# Soccer_Esp32.net
KiCad netlist of a schematic drawn in EasyEDA
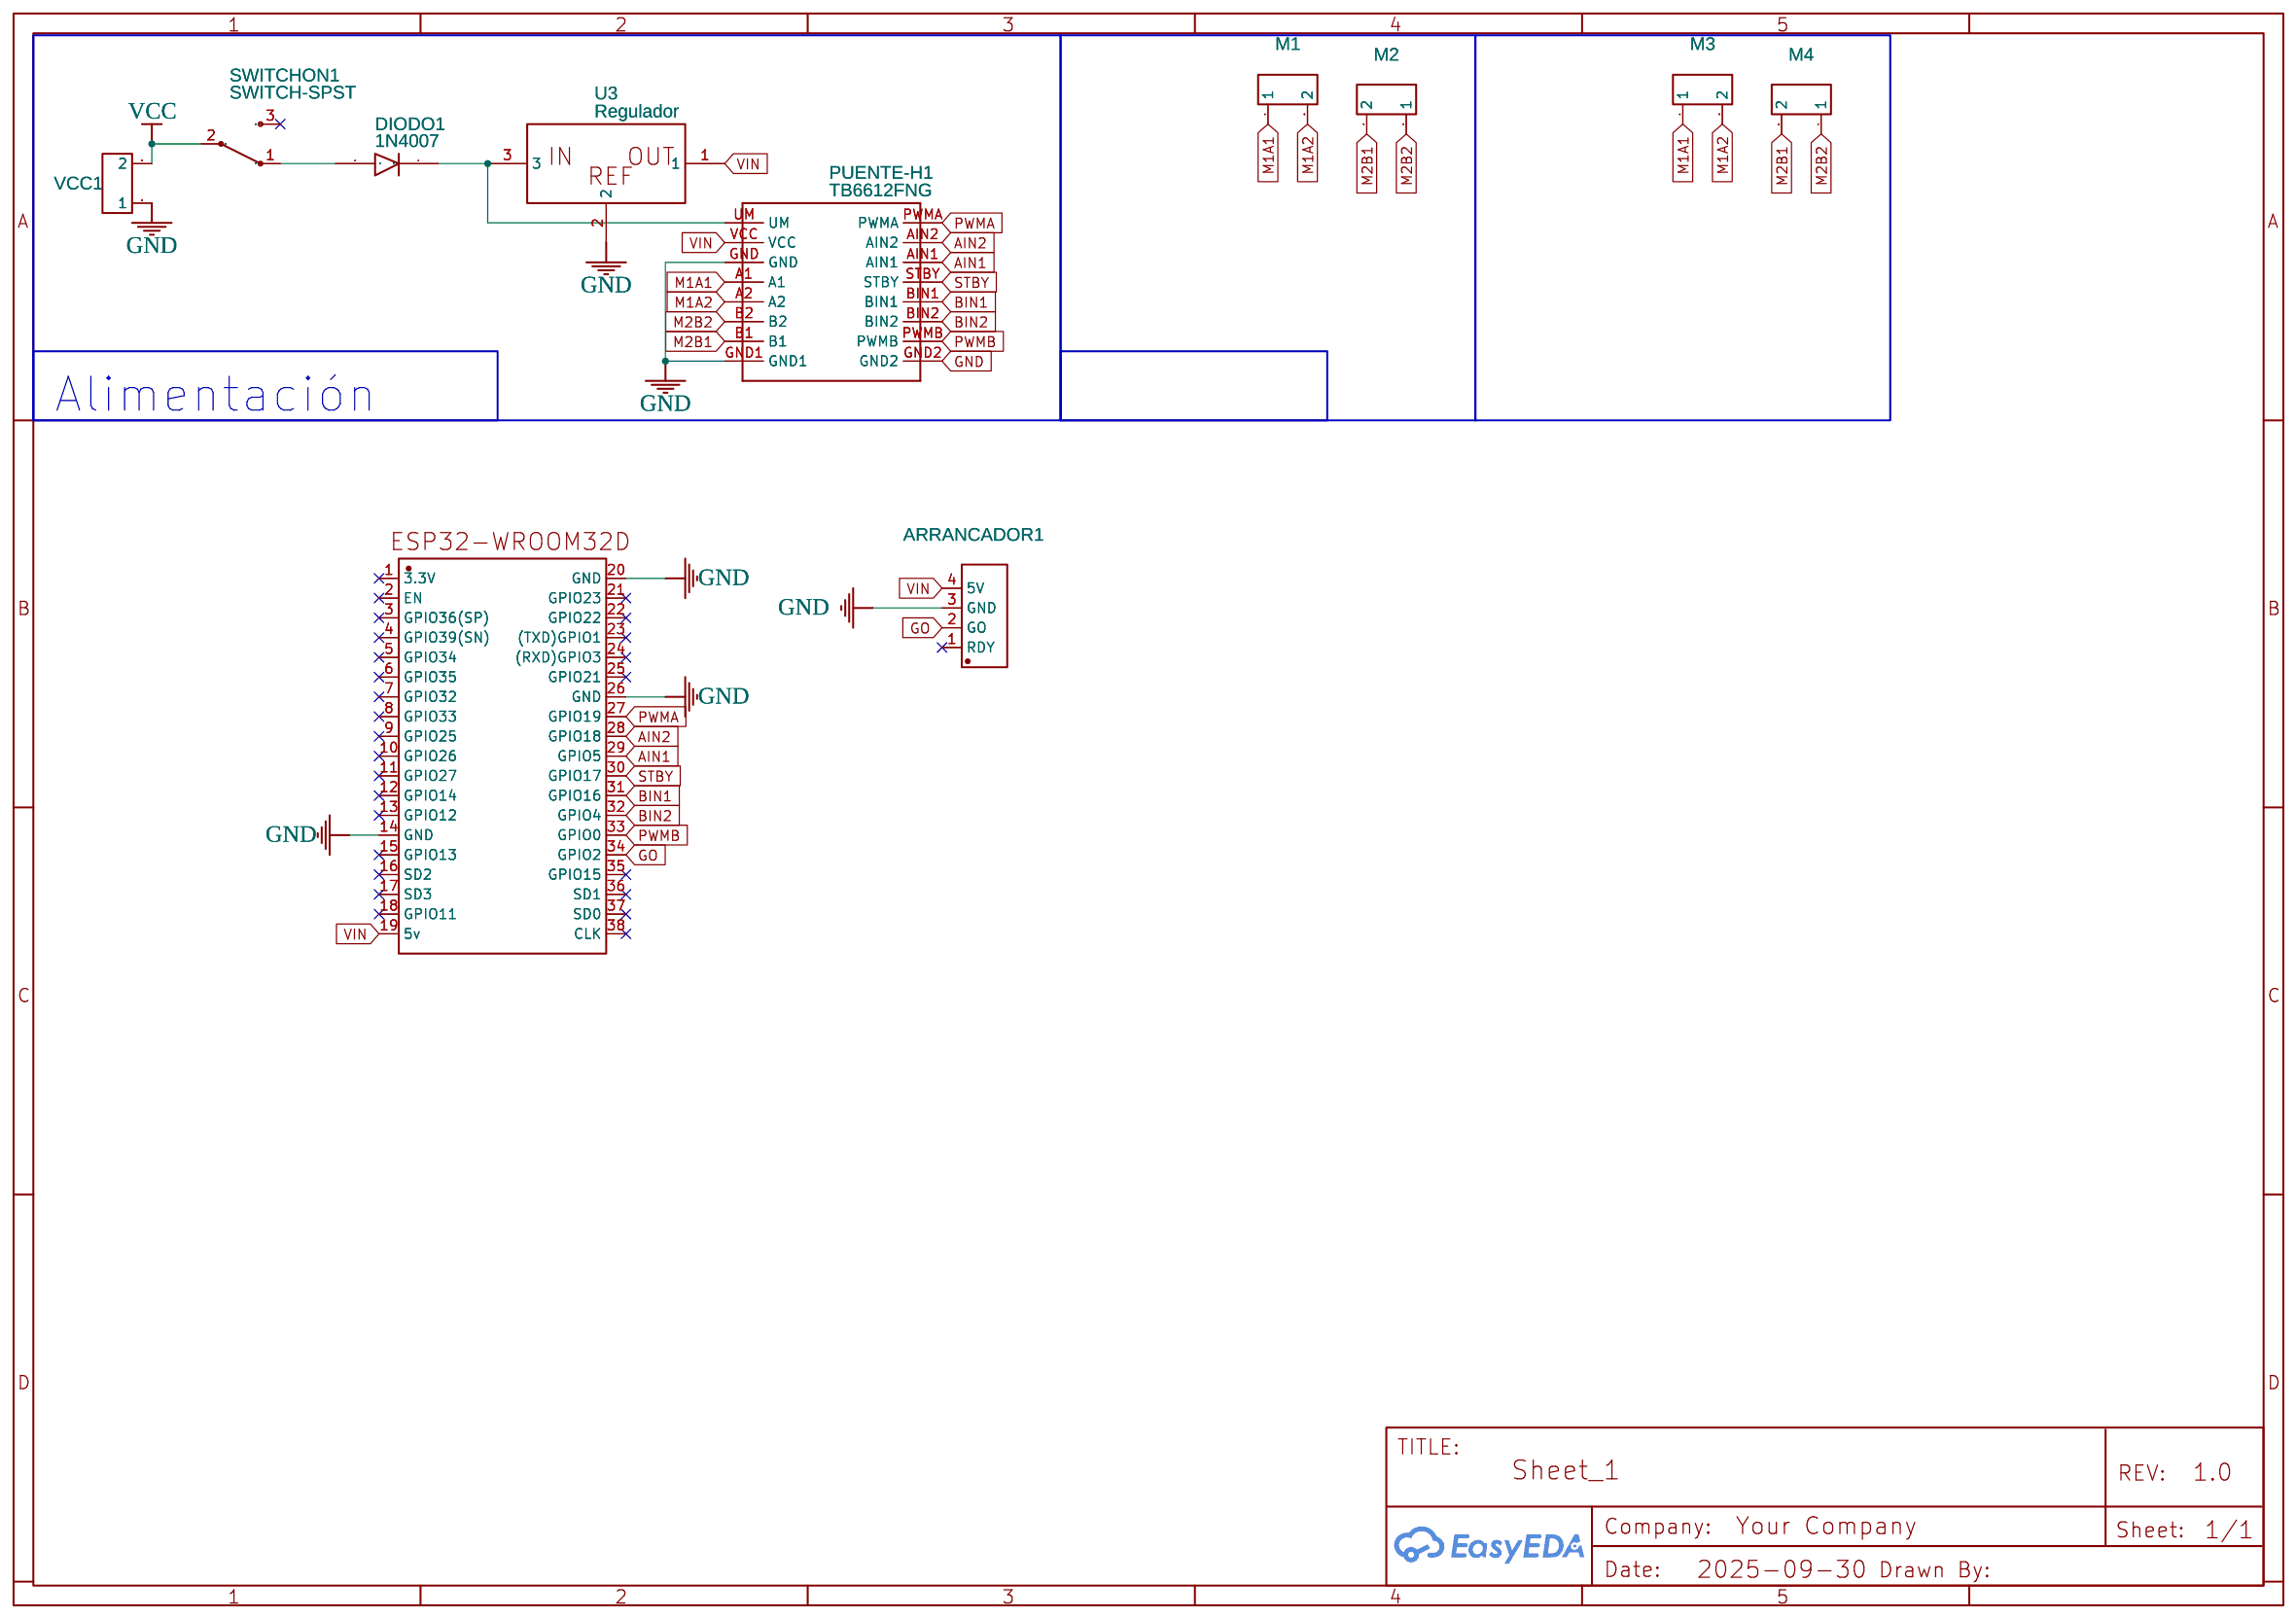
[diagram p0: schematic sheet]

(export (version "E")
  (design (tool "Eeschema 10.0.6"))
  (components
    (comp (ref "ARRANCADOR1") (value "HEADER 1X4P COPY") (libsource (lib "") (part "HEADER 1X4P COPY")))
    (comp (ref "DIODO1") (value "1N4007") (libsource (lib "") (part "1N4007")))
    (comp (ref "M1")
      (value "CONNECTOR 2 PINS")
      (fields
        (field (name "Manufacturer Part") "Female headerHDR1X8-2.54")
        (field (name "Manufacturer") "BOOMELE")
      )
      (libsource (lib "") (part "HEADER PAD 2X_1"))
    )
    (comp (ref "M2")
      (value "CONNECTOR 2 PINS")
      (fields
        (field (name "Manufacturer Part") "Female headerHDR1X8-2.54")
        (field (name "Manufacturer") "BOOMELE")
      )
      (libsource (lib "") (part "HEADER PAD 2X_2"))
    )
    (comp (ref "M3")
      (value "CONNECTOR 2 PINS")
      (fields
        (field (name "Manufacturer Part") "Female headerHDR1X8-2.54")
        (field (name "Manufacturer") "BOOMELE")
      )
      (libsource (lib "") (part "HEADER PAD 2X_1"))
    )
    (comp (ref "M4")
      (value "CONNECTOR 2 PINS")
      (fields
        (field (name "Manufacturer Part") "Female headerHDR1X8-2.54")
        (field (name "Manufacturer") "BOOMELE")
      )
      (libsource (lib "") (part "HEADER PAD 2X_2"))
    )
    (comp (ref "PUENTE-H1") (value "TB6612FNG") (libsource (lib "") (part "TB6612FNG")))
    (comp (ref "SWITCHON1") (value "SWITCH-SPST") (libsource (lib "") (part "SWITCH-SPST")))
    (comp (ref "U1")
      (value "ESP32WRoom32D")
      (fields (field (name "Manufacturer Part") "ESp32 38pin"))
      (libsource (lib "") (part "ESP32WRoom32D"))
    )
    (comp (ref "U3") (value "Regulador") (libsource (lib "") (part "Regulador")))
    (comp (ref "VCC1")
      (value "CONNECTOR 2 PINS")
      (fields
        (field (name "Manufacturer Part") "Female headerHDR1X8-2.54")
        (field (name "Manufacturer") "BOOMELE")
      )
      (libsource (lib "") (part "HEADER PAD 2X"))
    )
  )
  (nets
    (net (code "1") (name "AIN1") (class "Default")
      (node (ref "PUENTE-H1") (pin "AIN1") (pinfunction "AIN1_AIN1") (pintype "bidirectional"))
      (node (ref "U1") (pin "29") (pinfunction "GPIO5_29") (pintype "unspecified"))
    )
    (net (code "2") (name "AIN2") (class "Default")
      (node (ref "PUENTE-H1") (pin "AIN2") (pinfunction "AIN2_AIN2") (pintype "bidirectional"))
      (node (ref "U1") (pin "28") (pinfunction "GPIO18_28") (pintype "unspecified"))
    )
    (net (code "3") (name "BIN1") (class "Default")
      (node (ref "PUENTE-H1") (pin "BIN1") (pinfunction "BIN1_BIN1") (pintype "bidirectional"))
      (node (ref "U1") (pin "31") (pinfunction "GPIO16_31") (pintype "unspecified"))
    )
    (net (code "4") (name "BIN2") (class "Default")
      (node (ref "PUENTE-H1") (pin "BIN2") (pinfunction "BIN2_BIN2") (pintype "bidirectional"))
      (node (ref "U1") (pin "32") (pinfunction "GPIO4_32") (pintype "unspecified"))
    )
    (net (code "5") (name "GND") (class "Default")
      (node (ref "ARRANCADOR1") (pin "3") (pinfunction "GND_3") (pintype "unspecified"))
      (node (ref "PUENTE-H1") (pin "GND") (pinfunction "GND_GND") (pintype "bidirectional"))
      (node (ref "PUENTE-H1") (pin "GND1") (pinfunction "GND1_GND1") (pintype "bidirectional"))
      (node (ref "PUENTE-H1") (pin "GND2") (pinfunction "GND2_GND2") (pintype "bidirectional"))
      (node (ref "U1") (pin "14") (pinfunction "GND_14") (pintype "unspecified"))
      (node (ref "U1") (pin "20") (pinfunction "GND_20") (pintype "unspecified"))
      (node (ref "U1") (pin "26") (pinfunction "GND_26") (pintype "unspecified"))
      (node (ref "U3") (pin "2") (pinfunction "2_2") (pintype "unspecified"))
      (node (ref "VCC1") (pin "1") (pinfunction "1_1") (pintype "unspecified"))
    )
    (net (code "6") (name "GO") (class "Default")
      (node (ref "ARRANCADOR1") (pin "2") (pinfunction "GO_2") (pintype "unspecified"))
      (node (ref "U1") (pin "34") (pinfunction "GPIO2_34") (pintype "unspecified"))
    )
    (net (code "7") (name "M1A1") (class "Default")
      (node (ref "M1") (pin "1") (pinfunction "1_1") (pintype "unspecified"))
      (node (ref "M3") (pin "1") (pinfunction "1_1") (pintype "unspecified"))
      (node (ref "PUENTE-H1") (pin "A1") (pinfunction "A1_A1") (pintype "bidirectional"))
    )
    (net (code "8") (name "M1A2") (class "Default")
      (node (ref "M1") (pin "2") (pinfunction "2_2") (pintype "unspecified"))
      (node (ref "M3") (pin "2") (pinfunction "2_2") (pintype "unspecified"))
      (node (ref "PUENTE-H1") (pin "A2") (pinfunction "A2_A2") (pintype "bidirectional"))
    )
    (net (code "9") (name "M2B1") (class "Default")
      (node (ref "M2") (pin "2") (pinfunction "2_2") (pintype "unspecified"))
      (node (ref "M4") (pin "2") (pinfunction "2_2") (pintype "unspecified"))
      (node (ref "PUENTE-H1") (pin "B1") (pinfunction "B1_B1") (pintype "bidirectional"))
    )
    (net (code "10") (name "M2B2") (class "Default")
      (node (ref "M2") (pin "1") (pinfunction "1_1") (pintype "unspecified"))
      (node (ref "M4") (pin "1") (pinfunction "1_1") (pintype "unspecified"))
      (node (ref "PUENTE-H1") (pin "B2") (pinfunction "B2_B2") (pintype "bidirectional"))
    )
    (net (code "11") (name "Net-(DIODO1-Pad1)") (class "Default")
      (node (ref "DIODO1") (pin "1") (pinfunction "1_1") (pintype "unspecified"))
      (node (ref "PUENTE-H1") (pin "UM") (pinfunction "UM_UM") (pintype "bidirectional"))
      (node (ref "U3") (pin "3") (pinfunction "3_3") (pintype "unspecified"))
    )
    (net (code "12") (name "Net-(DIODO1-Pad2)") (class "Default")
      (node (ref "DIODO1") (pin "2") (pinfunction "2_2") (pintype "unspecified"))
      (node (ref "SWITCHON1") (pin "1") (pinfunction "1_1") (pintype "unspecified"))
    )
    (net (code "13") (name "PWMA") (class "Default")
      (node (ref "PUENTE-H1") (pin "PWMA") (pinfunction "PWMA_PWMA") (pintype "bidirectional"))
      (node (ref "U1") (pin "27") (pinfunction "GPIO19_27") (pintype "unspecified"))
    )
    (net (code "14") (name "PWMB") (class "Default")
      (node (ref "PUENTE-H1") (pin "PWMB") (pinfunction "PWMB_PWMB") (pintype "bidirectional"))
      (node (ref "U1") (pin "33") (pinfunction "GPIO0_33") (pintype "unspecified"))
    )
    (net (code "15") (name "STBY") (class "Default")
      (node (ref "PUENTE-H1") (pin "STBY") (pinfunction "STBY_STBY") (pintype "bidirectional"))
      (node (ref "U1") (pin "30") (pinfunction "GPIO17_30") (pintype "unspecified"))
    )
    (net (code "16") (name "VCC") (class "Default")
      (node (ref "SWITCHON1") (pin "2") (pinfunction "2_2") (pintype "unspecified"))
      (node (ref "VCC1") (pin "2") (pinfunction "2_2") (pintype "unspecified"))
    )
    (net (code "17") (name "VIN") (class "Default")
      (node (ref "ARRANCADOR1") (pin "4") (pinfunction "5V_4") (pintype "unspecified"))
      (node (ref "PUENTE-H1") (pin "VCC") (pinfunction "VCC_VCC") (pintype "bidirectional"))
      (node (ref "U1") (pin "19") (pinfunction "5v_19") (pintype "unspecified"))
      (node (ref "U3") (pin "1") (pinfunction "1_1") (pintype "unspecified"))
    )
    (net (code "18") (name "unconnected-(ARRANCADOR1-RDY-Pad1)") (class "Default")
      (node (ref "ARRANCADOR1") (pin "1") (pinfunction "RDY_1") (pintype "unspecified+no_connect"))
    )
    (net (code "19") (name "unconnected-(SWITCHON1-Pad3)") (class "Default")
      (node (ref "SWITCHON1") (pin "3") (pinfunction "3_3") (pintype "unspecified+no_connect"))
    )
    (net (code "20") (name "unconnected-(U1-(RXD)GPIO3-Pad24)") (class "Default")
      (node (ref "U1") (pin "24") (pinfunction "(RXD)GPIO3_24") (pintype "unspecified+no_connect"))
    )
    (net (code "21") (name "unconnected-(U1-(TXD)GPIO1-Pad23)") (class "Default")
      (node (ref "U1") (pin "23") (pinfunction "(TXD)GPIO1_23") (pintype "unspecified+no_connect"))
    )
    (net (code "22") (name "unconnected-(U1-3.3V-Pad1)") (class "Default")
      (node (ref "U1") (pin "1") (pinfunction "3.3V_1") (pintype "unspecified+no_connect"))
    )
    (net (code "23") (name "unconnected-(U1-CLK-Pad38)") (class "Default")
      (node (ref "U1") (pin "38") (pinfunction "CLK_38") (pintype "unspecified+no_connect"))
    )
    (net (code "24") (name "unconnected-(U1-EN-Pad2)") (class "Default")
      (node (ref "U1") (pin "2") (pinfunction "EN_2") (pintype "unspecified+no_connect"))
    )
    (net (code "25") (name "unconnected-(U1-GPIO11-Pad18)") (class "Default")
      (node (ref "U1") (pin "18") (pinfunction "GPIO11_18") (pintype "unspecified+no_connect"))
    )
    (net (code "26") (name "unconnected-(U1-GPIO12-Pad13)") (class "Default")
      (node (ref "U1") (pin "13") (pinfunction "GPIO12_13") (pintype "unspecified+no_connect"))
    )
    (net (code "27") (name "unconnected-(U1-GPIO13-Pad15)") (class "Default")
      (node (ref "U1") (pin "15") (pinfunction "GPIO13_15") (pintype "unspecified+no_connect"))
    )
    (net (code "28") (name "unconnected-(U1-GPIO14-Pad12)") (class "Default")
      (node (ref "U1") (pin "12") (pinfunction "GPIO14_12") (pintype "unspecified+no_connect"))
    )
    (net (code "29") (name "unconnected-(U1-GPIO15-Pad35)") (class "Default")
      (node (ref "U1") (pin "35") (pinfunction "GPIO15_35") (pintype "unspecified+no_connect"))
    )
    (net (code "30") (name "unconnected-(U1-GPIO21-Pad25)") (class "Default")
      (node (ref "U1") (pin "25") (pinfunction "GPIO21_25") (pintype "unspecified+no_connect"))
    )
    (net (code "31") (name "unconnected-(U1-GPIO22-Pad22)") (class "Default")
      (node (ref "U1") (pin "22") (pinfunction "GPIO22_22") (pintype "unspecified+no_connect"))
    )
    (net (code "32") (name "unconnected-(U1-GPIO23-Pad21)") (class "Default")
      (node (ref "U1") (pin "21") (pinfunction "GPIO23_21") (pintype "unspecified+no_connect"))
    )
    (net (code "33") (name "unconnected-(U1-GPIO25-Pad9)") (class "Default")
      (node (ref "U1") (pin "9") (pinfunction "GPIO25_9") (pintype "unspecified+no_connect"))
    )
    (net (code "34") (name "unconnected-(U1-GPIO26-Pad10)") (class "Default")
      (node (ref "U1") (pin "10") (pinfunction "GPIO26_10") (pintype "unspecified+no_connect"))
    )
    (net (code "35") (name "unconnected-(U1-GPIO27-Pad11)") (class "Default")
      (node (ref "U1") (pin "11") (pinfunction "GPIO27_11") (pintype "unspecified+no_connect"))
    )
    (net (code "36") (name "unconnected-(U1-GPIO32-Pad7)") (class "Default")
      (node (ref "U1") (pin "7") (pinfunction "GPIO32_7") (pintype "unspecified+no_connect"))
    )
    (net (code "37") (name "unconnected-(U1-GPIO33-Pad8)") (class "Default")
      (node (ref "U1") (pin "8") (pinfunction "GPIO33_8") (pintype "unspecified+no_connect"))
    )
    (net (code "38") (name "unconnected-(U1-GPIO34-Pad5)") (class "Default")
      (node (ref "U1") (pin "5") (pinfunction "GPIO34_5") (pintype "unspecified+no_connect"))
    )
    (net (code "39") (name "unconnected-(U1-GPIO35-Pad6)") (class "Default")
      (node (ref "U1") (pin "6") (pinfunction "GPIO35_6") (pintype "unspecified+no_connect"))
    )
    (net (code "40") (name "unconnected-(U1-GPIO36(SP)-Pad3)") (class "Default")
      (node (ref "U1") (pin "3") (pinfunction "GPIO36(SP)_3") (pintype "unspecified+no_connect"))
    )
    (net (code "41") (name "unconnected-(U1-GPIO39(SN)-Pad4)") (class "Default")
      (node (ref "U1") (pin "4") (pinfunction "GPIO39(SN)_4") (pintype "unspecified+no_connect"))
    )
    (net (code "42") (name "unconnected-(U1-SD0-Pad37)") (class "Default")
      (node (ref "U1") (pin "37") (pinfunction "SD0_37") (pintype "unspecified+no_connect"))
    )
    (net (code "43") (name "unconnected-(U1-SD1-Pad36)") (class "Default")
      (node (ref "U1") (pin "36") (pinfunction "SD1_36") (pintype "unspecified+no_connect"))
    )
    (net (code "44") (name "unconnected-(U1-SD2-Pad16)") (class "Default")
      (node (ref "U1") (pin "16") (pinfunction "SD2_16") (pintype "unspecified+no_connect"))
    )
    (net (code "45") (name "unconnected-(U1-SD3-Pad17)") (class "Default")
      (node (ref "U1") (pin "17") (pinfunction "SD3_17") (pintype "unspecified+no_connect"))
    )
  )
)
